# control.net
KiCad netlist of a schematic drawn in EAGLE
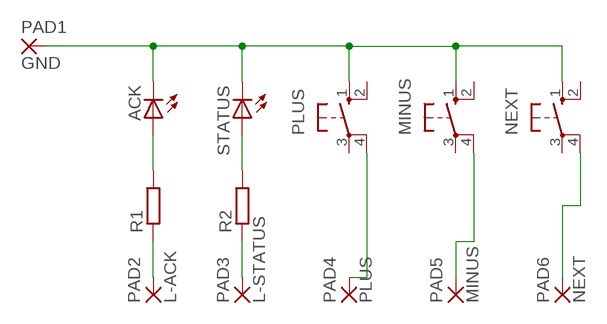
[diagram p0: schematic, sheet 1]

(export (version "E")
  (design (tool "Eeschema 10.0.6"))
  (components
    (comp (ref "ACK")
      (value "LED3MM")
      (footprint "eagle-import:LED3MM")
      (libsource (lib "eagle-import") (part "LED3MM"))
    )
    (comp (ref "MINUS")
      (value "10-XX")
      (footprint "eagle-import:B3F-10XX")
      (libsource (lib "eagle-import") (part "10-XX"))
    )
    (comp (ref "NEXT")
      (value "10-XX")
      (footprint "eagle-import:B3F-10XX")
      (libsource (lib "eagle-import") (part "10-XX"))
    )
    (comp (ref "PAD1")
      (value "GND")
      (footprint "eagle-import:SMD1,27-2,54")
      (libsource (lib "eagle-import") (part "SMD2"))
    )
    (comp (ref "PAD2")
      (value "L-ACK")
      (footprint "eagle-import:SMD1,27-2,54")
      (libsource (lib "eagle-import") (part "SMD2"))
    )
    (comp (ref "PAD3")
      (value "L-STATUS")
      (footprint "eagle-import:SMD1,27-2,54")
      (libsource (lib "eagle-import") (part "SMD2"))
    )
    (comp (ref "PAD4")
      (value "PLUS")
      (footprint "eagle-import:SMD1,27-2,54")
      (libsource (lib "eagle-import") (part "SMD2"))
    )
    (comp (ref "PAD5")
      (value "MINUS")
      (footprint "eagle-import:SMD1,27-2,54")
      (libsource (lib "eagle-import") (part "SMD2"))
    )
    (comp (ref "PAD6")
      (value "NEXT")
      (footprint "eagle-import:SMD1,27-2,54")
      (libsource (lib "eagle-import") (part "SMD2"))
    )
    (comp (ref "PLUS")
      (value "10-XX")
      (footprint "eagle-import:B3F-10XX")
      (libsource (lib "eagle-import") (part "10-XX"))
    )
    (comp (ref "R1")
      (value "R-EU_R0805")
      (footprint "eagle-import:R0805")
      (libsource (lib "eagle-import") (part "R-EU_R0805"))
    )
    (comp (ref "R2")
      (value "R-EU_R0805")
      (footprint "eagle-import:R0805")
      (libsource (lib "eagle-import") (part "R-EU_R0805"))
    )
    (comp (ref "STATUS")
      (value "LED3MM")
      (footprint "eagle-import:LED3MM")
      (libsource (lib "eagle-import") (part "LED3MM"))
    )
  )
  (nets
    (net (code "1") (name "Net-(ACK-C)") (class "Default")
      (node (ref "ACK") (pin "K") (pinfunction "C_K") (pintype "passive"))
      (node (ref "MINUS") (pin "1") (pinfunction "S_1") (pintype "passive"))
      (node (ref "NEXT") (pin "1") (pinfunction "S_1") (pintype "passive"))
      (node (ref "PAD1") (pin "1") (pinfunction "P_1") (pintype "passive"))
      (node (ref "PLUS") (pin "1") (pinfunction "S_1") (pintype "passive"))
      (node (ref "STATUS") (pin "K") (pinfunction "C_K") (pintype "passive"))
    )
    (net (code "2") (name "Net-(ACK-PadA)") (class "Default")
      (node (ref "ACK") (pin "A") (pinfunction "A_A") (pintype "passive"))
      (node (ref "R1") (pin "2") (pinfunction "2_2") (pintype "passive"))
    )
    (net (code "3") (name "Net-(MINUS-P1)") (class "Default")
      (node (ref "MINUS") (pin "4") (pinfunction "P1_4") (pintype "passive"))
      (node (ref "PAD5") (pin "1") (pinfunction "P_1") (pintype "passive"))
    )
    (net (code "4") (name "Net-(NEXT-P1)") (class "Default")
      (node (ref "NEXT") (pin "4") (pinfunction "P1_4") (pintype "passive"))
      (node (ref "PAD6") (pin "1") (pinfunction "P_1") (pintype "passive"))
    )
    (net (code "5") (name "Net-(PAD2-P)") (class "Default")
      (node (ref "PAD2") (pin "1") (pinfunction "P_1") (pintype "passive"))
      (node (ref "R1") (pin "1") (pinfunction "1_1") (pintype "passive"))
    )
    (net (code "6") (name "Net-(PAD3-P)") (class "Default")
      (node (ref "PAD3") (pin "1") (pinfunction "P_1") (pintype "passive"))
      (node (ref "R2") (pin "1") (pinfunction "1_1") (pintype "passive"))
    )
    (net (code "7") (name "Net-(PAD4-P)") (class "Default")
      (node (ref "PAD4") (pin "1") (pinfunction "P_1") (pintype "passive"))
      (node (ref "PLUS") (pin "4") (pinfunction "P1_4") (pintype "passive"))
    )
    (net (code "8") (name "Net-(R2-Pad2)") (class "Default")
      (node (ref "R2") (pin "2") (pinfunction "2_2") (pintype "passive"))
      (node (ref "STATUS") (pin "A") (pinfunction "A_A") (pintype "passive"))
    )
    (net (code "9") (name "unconnected-(MINUS-P-Pad3)") (class "Default")
      (node (ref "MINUS") (pin "3") (pinfunction "P_3") (pintype "passive"))
    )
    (net (code "10") (name "unconnected-(MINUS-S1-Pad2)") (class "Default")
      (node (ref "MINUS") (pin "2") (pinfunction "S1_2") (pintype "passive"))
    )
    (net (code "11") (name "unconnected-(NEXT-P-Pad3)") (class "Default")
      (node (ref "NEXT") (pin "3") (pinfunction "P_3") (pintype "passive"))
    )
    (net (code "12") (name "unconnected-(NEXT-S1-Pad2)") (class "Default")
      (node (ref "NEXT") (pin "2") (pinfunction "S1_2") (pintype "passive"))
    )
    (net (code "13") (name "unconnected-(PLUS-P-Pad3)") (class "Default")
      (node (ref "PLUS") (pin "3") (pinfunction "P_3") (pintype "passive"))
    )
    (net (code "14") (name "unconnected-(PLUS-S1-Pad2)") (class "Default")
      (node (ref "PLUS") (pin "2") (pinfunction "S1_2") (pintype "passive"))
    )
  )
)
